# board1_attiny85.net
KiCad netlist of a schematic drawn in EAGLE
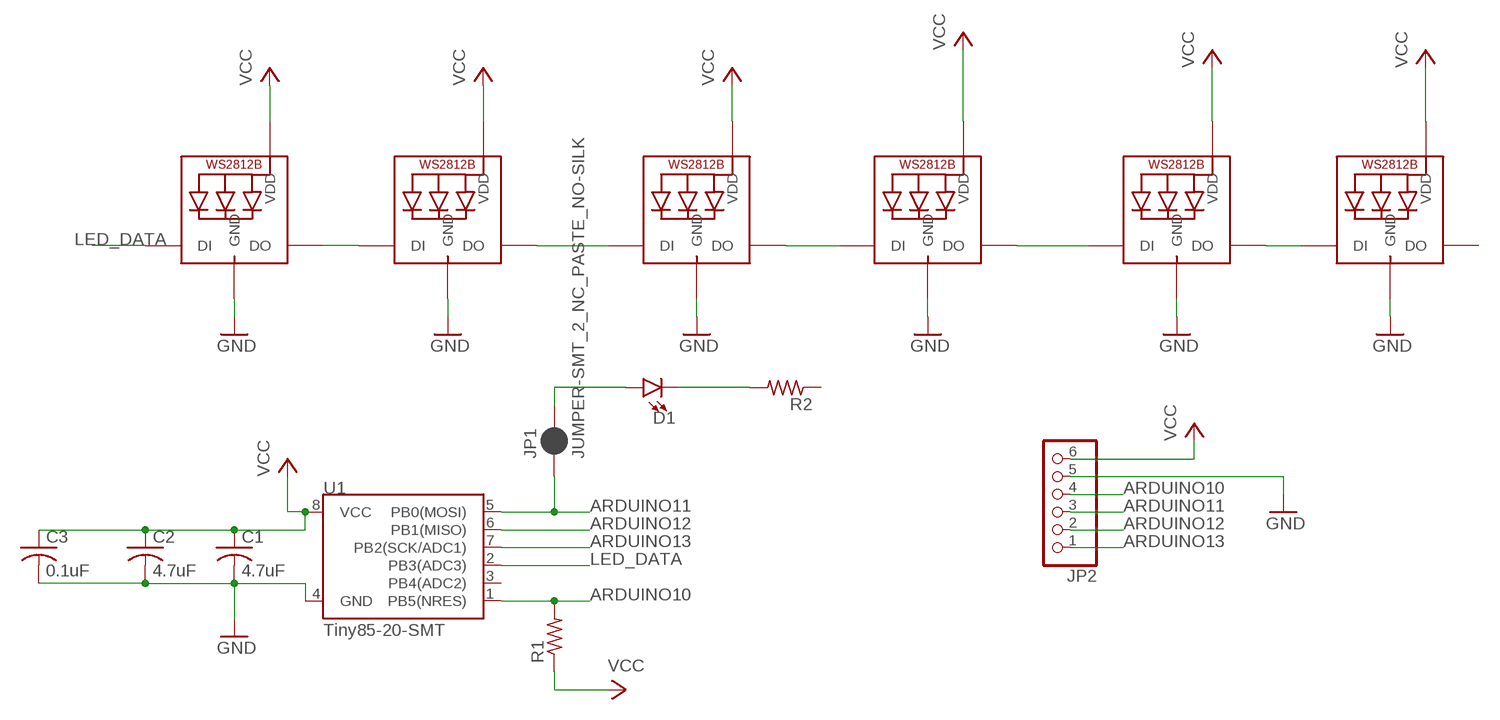
[diagram p0: schematic, sheet 1]

(export (version "E")
  (design (tool "Eeschema 10.0.6"))
  (components
    (comp (ref "C1")
      (value "4.7uF")
      (footprint "eagle-import:C0603")
      (libsource (lib "eagle-import") (part "C-USC0603"))
    )
    (comp (ref "C2")
      (value "4.7uF")
      (footprint "eagle-import:C0603")
      (libsource (lib "eagle-import") (part "C-USC0603"))
    )
    (comp (ref "C3")
      (value "0.1uF")
      (footprint "eagle-import:C0603")
      (libsource (lib "eagle-import") (part "C-USC0603"))
    )
    (comp (ref "D1")
      (value "LED0603")
      (footprint "eagle-import:LED-0603")
      (libsource (lib "eagle-import") (part "LED0603"))
    )
    (comp (ref "JP1")
      (value "JUMPER-SMT_2_NC_PASTE_NO-SILK")
      (footprint "eagle-import:SMT-JUMPER_2_NC_PASTE_NO-SILK")
      (libsource (lib "eagle-import") (part "JUMPER-SMT_2_NC_PASTE_NO-SILK"))
    )
    (comp (ref "JP2")
      (value "PINHD-1X6")
      (footprint "eagle-import:1X06")
      (libsource (lib "eagle-import") (part "PINHD-1X6"))
    )
    (comp (ref "LED1")
      (value "WS2812B5050")
      (footprint "eagle-import:WS2812B")
      (libsource (lib "eagle-import") (part "WS2812B5050"))
    )
    (comp (ref "LED2")
      (value "WS2812B5050")
      (footprint "eagle-import:WS2812B")
      (libsource (lib "eagle-import") (part "WS2812B5050"))
    )
    (comp (ref "LED3")
      (value "WS2812B5050")
      (footprint "eagle-import:WS2812B")
      (libsource (lib "eagle-import") (part "WS2812B5050"))
    )
    (comp (ref "LED4")
      (value "WS2812B5050")
      (footprint "eagle-import:WS2812B")
      (libsource (lib "eagle-import") (part "WS2812B5050"))
    )
    (comp (ref "LED5")
      (value "WS2812B5050")
      (footprint "eagle-import:WS2812B")
      (libsource (lib "eagle-import") (part "WS2812B5050"))
    )
    (comp (ref "LED6")
      (value "WS2812B5050")
      (footprint "eagle-import:WS2812B")
      (libsource (lib "eagle-import") (part "WS2812B5050"))
    )
    (comp (ref "R1")
      (value "R-US_R0603")
      (footprint "eagle-import:R0603")
      (libsource (lib "eagle-import") (part "R-US_R0603"))
    )
    (comp (ref "R2")
      (value "R-US_R0603")
      (footprint "eagle-import:R0603")
      (libsource (lib "eagle-import") (part "R-US_R0603"))
    )
    (comp (ref "U1")
      (value "Tiny85-20-SMT")
      (footprint "eagle-import:SO08-EIAJ_MCU")
      (libsource (lib "eagle-import") (part "ATTINY45TINY85-20-SMT"))
    )
  )
  (nets
    (net (code "1") (name "/ARDUINO10") (class "Default")
      (node (ref "JP2") (pin "4") (pinfunction "4_4") (pintype "passive"))
      (node (ref "R1") (pin "2") (pinfunction "2_2") (pintype "passive"))
      (node (ref "U1") (pin "1") (pinfunction "PB5(NRES)_1") (pintype "bidirectional"))
    )
    (net (code "2") (name "/ARDUINO11") (class "Default")
      (node (ref "JP1") (pin "1") (pinfunction "1_1") (pintype "passive"))
      (node (ref "JP2") (pin "3") (pinfunction "3_3") (pintype "passive"))
      (node (ref "U1") (pin "5") (pinfunction "PB0(MOSI)_5") (pintype "bidirectional"))
    )
    (net (code "3") (name "/ARDUINO12") (class "Default")
      (node (ref "JP2") (pin "2") (pinfunction "2_2") (pintype "passive"))
      (node (ref "U1") (pin "6") (pinfunction "PB1(MISO)_6") (pintype "bidirectional"))
    )
    (net (code "4") (name "/ARDUINO13") (class "Default")
      (node (ref "JP2") (pin "1") (pinfunction "1_1") (pintype "passive"))
      (node (ref "U1") (pin "7") (pinfunction "PB2(SCK/ADC1)_7") (pintype "bidirectional"))
    )
    (net (code "5") (name "/LED_DATA") (class "Default")
      (node (ref "LED1") (pin "4-DIN") (pinfunction "DI_4-DIN") (pintype "input"))
      (node (ref "U1") (pin "2") (pinfunction "PB3(ADC3)_2") (pintype "bidirectional"))
    )
    (net (code "6") (name "GND") (class "Default")
      (node (ref "C1") (pin "2") (pinfunction "2_2") (pintype "passive"))
      (node (ref "C2") (pin "2") (pinfunction "2_2") (pintype "passive"))
      (node (ref "C3") (pin "2") (pinfunction "2_2") (pintype "passive"))
      (node (ref "JP2") (pin "5") (pinfunction "5_5") (pintype "passive"))
      (node (ref "LED1") (pin "3-GND") (pinfunction "GND_3-GND") (pintype "power_in"))
      (node (ref "LED2") (pin "3-GND") (pinfunction "GND_3-GND") (pintype "power_in"))
      (node (ref "LED3") (pin "3-GND") (pinfunction "GND_3-GND") (pintype "power_in"))
      (node (ref "LED4") (pin "3-GND") (pinfunction "GND_3-GND") (pintype "power_in"))
      (node (ref "LED5") (pin "3-GND") (pinfunction "GND_3-GND") (pintype "power_in"))
      (node (ref "LED6") (pin "3-GND") (pinfunction "GND_3-GND") (pintype "power_in"))
      (node (ref "U1") (pin "4") (pinfunction "GND_4") (pintype "bidirectional"))
    )
    (net (code "7") (name "Net-(D1-PadA)") (class "Default")
      (node (ref "D1") (pin "A") (pinfunction "A_A") (pintype "passive"))
      (node (ref "JP1") (pin "2") (pinfunction "2_2") (pintype "passive"))
    )
    (net (code "8") (name "Net-(D1-PadC)") (class "Default")
      (node (ref "D1") (pin "C") (pinfunction "C_C") (pintype "passive"))
      (node (ref "R2") (pin "2") (pinfunction "2_2") (pintype "passive"))
    )
    (net (code "9") (name "Net-(LED1-DO)") (class "Default")
      (node (ref "LED1") (pin "2-DOUT") (pinfunction "DO_2-DOUT") (pintype "output"))
      (node (ref "LED2") (pin "4-DIN") (pinfunction "DI_4-DIN") (pintype "input"))
    )
    (net (code "10") (name "Net-(LED2-DO)") (class "Default")
      (node (ref "LED2") (pin "2-DOUT") (pinfunction "DO_2-DOUT") (pintype "output"))
      (node (ref "LED3") (pin "4-DIN") (pinfunction "DI_4-DIN") (pintype "input"))
    )
    (net (code "11") (name "Net-(LED3-DO)") (class "Default")
      (node (ref "LED3") (pin "2-DOUT") (pinfunction "DO_2-DOUT") (pintype "output"))
      (node (ref "LED4") (pin "4-DIN") (pinfunction "DI_4-DIN") (pintype "input"))
    )
    (net (code "12") (name "Net-(LED4-DO)") (class "Default")
      (node (ref "LED4") (pin "2-DOUT") (pinfunction "DO_2-DOUT") (pintype "output"))
      (node (ref "LED5") (pin "4-DIN") (pinfunction "DI_4-DIN") (pintype "input"))
    )
    (net (code "13") (name "Net-(LED5-DO)") (class "Default")
      (node (ref "LED5") (pin "2-DOUT") (pinfunction "DO_2-DOUT") (pintype "output"))
      (node (ref "LED6") (pin "4-DIN") (pinfunction "DI_4-DIN") (pintype "input"))
    )
    (net (code "14") (name "VCC") (class "Default")
      (node (ref "C1") (pin "1") (pinfunction "1_1") (pintype "passive"))
      (node (ref "C2") (pin "1") (pinfunction "1_1") (pintype "passive"))
      (node (ref "C3") (pin "1") (pinfunction "1_1") (pintype "passive"))
      (node (ref "JP2") (pin "6") (pinfunction "6_6") (pintype "passive"))
      (node (ref "LED1") (pin "1-VDD") (pinfunction "VDD_1-VDD") (pintype "power_in"))
      (node (ref "LED2") (pin "1-VDD") (pinfunction "VDD_1-VDD") (pintype "power_in"))
      (node (ref "LED3") (pin "1-VDD") (pinfunction "VDD_1-VDD") (pintype "power_in"))
      (node (ref "LED4") (pin "1-VDD") (pinfunction "VDD_1-VDD") (pintype "power_in"))
      (node (ref "LED5") (pin "1-VDD") (pinfunction "VDD_1-VDD") (pintype "power_in"))
      (node (ref "LED6") (pin "1-VDD") (pinfunction "VDD_1-VDD") (pintype "power_in"))
      (node (ref "R1") (pin "1") (pinfunction "1_1") (pintype "passive"))
      (node (ref "U1") (pin "8") (pinfunction "VCC_8") (pintype "bidirectional"))
    )
    (net (code "15") (name "unconnected-(LED6-DO-Pad2-DOUT)") (class "Default")
      (node (ref "LED6") (pin "2-DOUT") (pinfunction "DO_2-DOUT") (pintype "output"))
    )
    (net (code "16") (name "unconnected-(R2-Pad1)") (class "Default")
      (node (ref "R2") (pin "1") (pinfunction "1_1") (pintype "passive"))
    )
    (net (code "17") (name "unconnected-(U1-PB4(ADC2)-Pad3)") (class "Default")
      (node (ref "U1") (pin "3") (pinfunction "PB4(ADC2)_3") (pintype "bidirectional"))
    )
  )
)
